# Sediment_Board_single.net
KiCad netlist of a schematic drawn in EAGLE
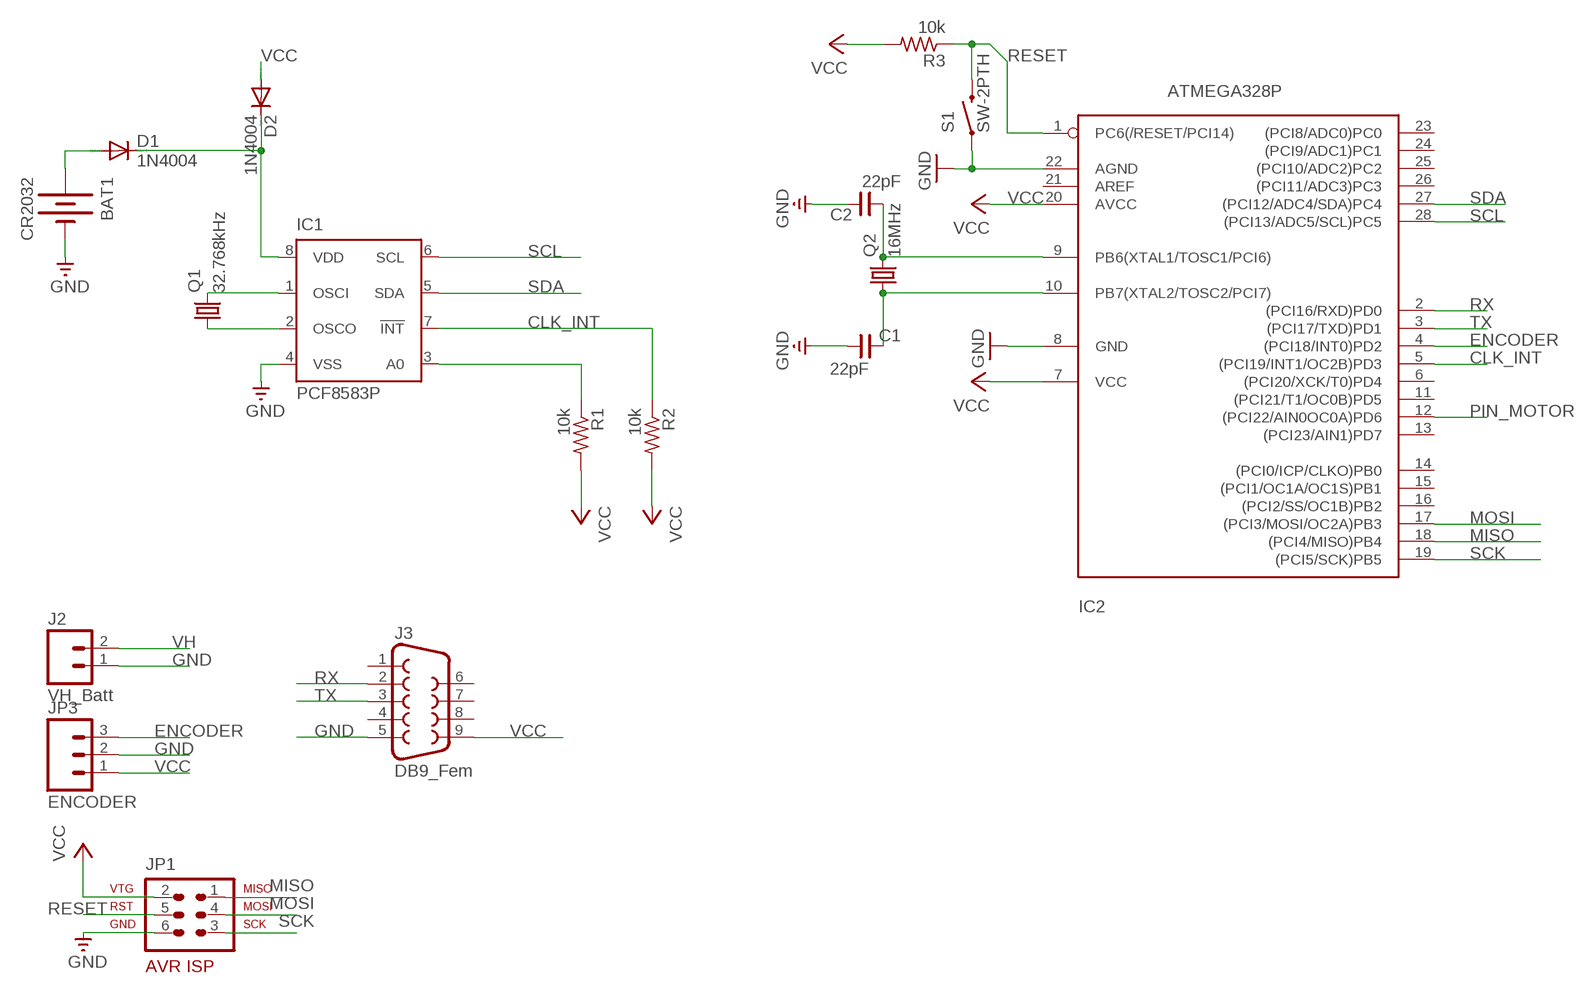
[diagram p0: schematic, sheet 1]
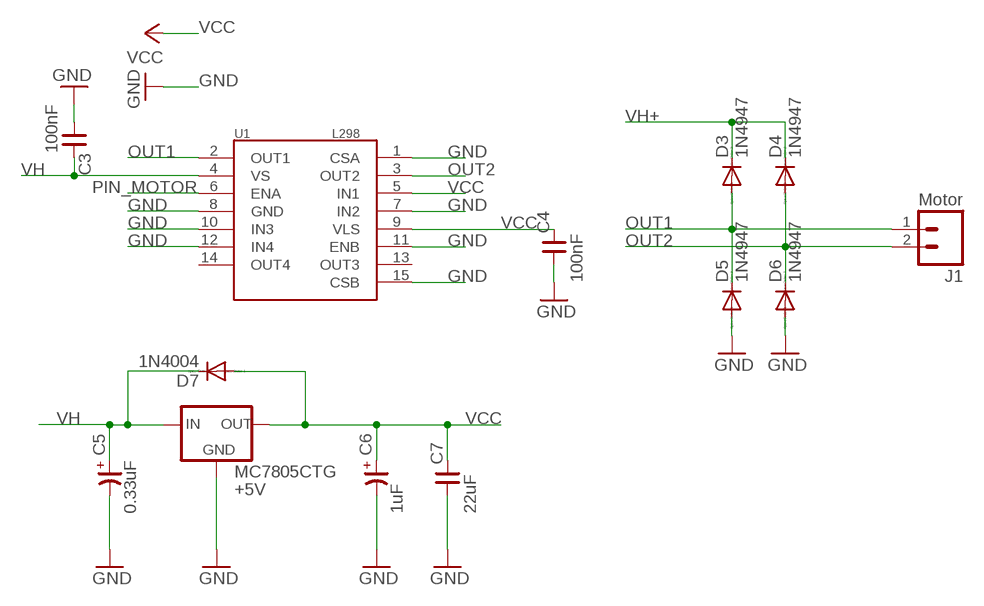
[diagram p1: schematic, sheet 2]

(export (version "E")
  (design (tool "Eeschema 10.0.6"))
  (components
    (comp (ref "C3")
      (value "100nF")
      (footprint "eagle-import:C025-050X025")
      (libsource (lib "eagle-import") (part "CNP-C025-050X025"))
    )
    (comp (ref "C4")
      (value "100nF")
      (footprint "eagle-import:C025-050X025")
      (libsource (lib "eagle-import") (part "CNP-C025-050X025"))
    )
    (comp (ref "C5")
      (value "0.33uF")
      (footprint "eagle-import:TT-025-040")
      (libsource (lib "eagle-import") (part "CP-TT025-040"))
    )
    (comp (ref "C6")
      (value "1uF")
      (footprint "eagle-import:TT-025-040")
      (libsource (lib "eagle-import") (part "CP-TT025-040"))
    )
    (comp (ref "C7")
      (value "22uF")
      (footprint "eagle-import:C025-050X025")
      (libsource (lib "eagle-import") (part "CNP-C025-050X025"))
    )
    (comp (ref "D3")
      (value "1N4947")
      (footprint "eagle-import:DO41-10")
      (libsource (lib "eagle-import") (part "1N4942"))
    )
    (comp (ref "D4")
      (value "1N4947")
      (footprint "eagle-import:DO41-10")
      (libsource (lib "eagle-import") (part "1N4942"))
    )
    (comp (ref "D5")
      (value "1N4947")
      (footprint "eagle-import:DO41-10")
      (libsource (lib "eagle-import") (part "1N4942"))
    )
    (comp (ref "D6")
      (value "1N4947")
      (footprint "eagle-import:DO41-10")
      (libsource (lib "eagle-import") (part "1N4942"))
    )
    (comp (ref "D7")
      (value "1N4004")
      (footprint "eagle-import:DO41-10")
      (libsource (lib "eagle-import") (part "1N4004"))
    )
    (comp (ref "J1")
      (value "Motor")
      (footprint "eagle-import:SCREWTERMINAL-3.5MM-2")
      (libsource (lib "eagle-import") (part "M023.5MM"))
    )
    (comp (ref "MC7805CTG")
      (value "+5V")
      (footprint "eagle-import:78XXL")
      (libsource (lib "eagle-import") (part "V_REG_78XXSIDE"))
    )
    (comp (ref "U1")
      (value "L298")
      (footprint "eagle-import:MULTIWATT15")
      (libsource (lib "eagle-import") (part "L298"))
    )
    (comp (ref "BAT1")
      (value "CR2032")
      (footprint "eagle-import:BATTCOM_20MM_PTH")
      (libsource (lib "eagle-import") (part "BATTERY20PTH"))
    )
    (comp (ref "C1")
      (value "22pF")
      (footprint "eagle-import:C025-050X025")
      (libsource (lib "eagle-import") (part "CNP-C025-050X025"))
    )
    (comp (ref "C2")
      (value "22pF")
      (footprint "eagle-import:C025-050X025")
      (libsource (lib "eagle-import") (part "CNP-C025-050X025"))
    )
    (comp (ref "D1")
      (value "1N4004")
      (footprint "eagle-import:DO41-10")
      (libsource (lib "eagle-import") (part "1N4004"))
    )
    (comp (ref "D2")
      (value "1N4004")
      (footprint "eagle-import:DO41-10")
      (libsource (lib "eagle-import") (part "1N4004"))
    )
    (comp (ref "IC1")
      (value "PCF8583P")
      (footprint "eagle-import:DIL08")
      (libsource (lib "eagle-import") (part "PCF8583P"))
    )
    (comp (ref "IC2")
      (value "ATMEGA328P")
      (footprint "eagle-import:DIL28-3-ROUND")
      (libsource (lib "eagle-import") (part "ATMEGA328PROUND"))
    )
    (comp (ref "J2")
      (value "VH_Batt")
      (footprint "eagle-import:SCREWTERMINAL-3.5MM-2")
      (libsource (lib "eagle-import") (part "M023.5MM"))
    )
    (comp (ref "J3")
      (value "DB9_Fem")
      (footprint "eagle-import:DB9")
      (libsource (lib "eagle-import") (part "DB9FEMALE"))
    )
    (comp (ref "JP1")
      (value "AVR-ISP-6")
      (footprint "eagle-import:AVR-ISP-6")
      (libsource (lib "eagle-import") (part "AVR-ISP-6"))
    )
    (comp (ref "JP3")
      (value "ENCODER")
      (footprint "eagle-import:MOLEX-1X3")
      (libsource (lib "eagle-import") (part "M03POLAR"))
    )
    (comp (ref "Q1")
      (value "32.768kHz")
      (footprint "eagle-import:TC26H")
      (libsource (lib "eagle-import") (part "CRYSTALTC26H"))
    )
    (comp (ref "Q2")
      (value "16MHz")
      (footprint "eagle-import:HC49U70")
      (libsource (lib "eagle-import") (part "CRYSTALHC49U70"))
    )
    (comp (ref "R1")
      (value "10k")
      (footprint "eagle-import:0207_10")
      (libsource (lib "eagle-import") (part "R-US_0207/10"))
    )
    (comp (ref "R2")
      (value "10k")
      (footprint "eagle-import:0207_10")
      (libsource (lib "eagle-import") (part "R-US_0207/10"))
    )
    (comp (ref "R3")
      (value "10k")
      (footprint "eagle-import:0207_10")
      (libsource (lib "eagle-import") (part "R-US_0207/10"))
    )
    (comp (ref "S1")
      (value "SW-2PTH")
      (footprint "eagle-import:TACTILE-PTH")
      (libsource (lib "eagle-import") (part "SWITCH-MOMENTARY-2PTH"))
    )
  )
  (nets
    (net (code "1") (name "CLK_INT") (class "Default")
      (node (ref "IC1") (pin "7") (pinfunction "~{INT}_7") (pintype "open_collector"))
      (node (ref "IC2") (pin "5") (pinfunction "(PCI19/INT1/OC2B)PD3_5") (pintype "bidirectional"))
      (node (ref "R2") (pin "1") (pinfunction "1_1") (pintype "passive"))
    )
    (net (code "2") (name "ENCODER") (class "Default")
      (node (ref "IC2") (pin "4") (pinfunction "(PCI18/INT0)PD2_4") (pintype "bidirectional"))
      (node (ref "JP3") (pin "3") (pinfunction "3_3") (pintype "passive"))
    )
    (net (code "3") (name "GND") (class "Default")
      (node (ref "BAT1") (pin "2") (pinfunction "-_2") (pintype "power_in"))
      (node (ref "C1") (pin "1") (pinfunction "1_1") (pintype "passive"))
      (node (ref "C2") (pin "2") (pinfunction "2_2") (pintype "passive"))
      (node (ref "C3") (pin "1") (pinfunction "1_1") (pintype "passive"))
      (node (ref "C4") (pin "1") (pinfunction "1_1") (pintype "passive"))
      (node (ref "C5") (pin "-") (pinfunction "-_-") (pintype "passive"))
      (node (ref "C6") (pin "-") (pinfunction "-_-") (pintype "passive"))
      (node (ref "C7") (pin "1") (pinfunction "1_1") (pintype "passive"))
      (node (ref "D5") (pin "A") (pinfunction "A_A") (pintype "passive"))
      (node (ref "D6") (pin "A") (pinfunction "A_A") (pintype "passive"))
      (node (ref "IC1") (pin "4") (pinfunction "VSS_4") (pintype "power_in"))
      (node (ref "IC2") (pin "22") (pinfunction "AGND_22") (pintype "bidirectional"))
      (node (ref "IC2") (pin "8") (pinfunction "GND_8") (pintype "bidirectional"))
      (node (ref "J2") (pin "1") (pinfunction "1_1") (pintype "passive"))
      (node (ref "J3") (pin "5") (pinfunction "5_5") (pintype "passive"))
      (node (ref "JP1") (pin "6") (pinfunction "6_6") (pintype "passive"))
      (node (ref "JP3") (pin "2") (pinfunction "2_2") (pintype "passive"))
      (node (ref "MC7805CTG") (pin "GND") (pinfunction "GND_GND") (pintype "input"))
      (node (ref "S1") (pin "1") (pinfunction "1_1") (pintype "passive"))
      (node (ref "U1") (pin "1") (pinfunction "CSA_1") (pintype "bidirectional"))
      (node (ref "U1") (pin "10") (pinfunction "IN3_10") (pintype "bidirectional"))
      (node (ref "U1") (pin "11") (pinfunction "ENB_11") (pintype "bidirectional"))
      (node (ref "U1") (pin "12") (pinfunction "IN4_12") (pintype "bidirectional"))
      (node (ref "U1") (pin "15") (pinfunction "CSB_15") (pintype "bidirectional"))
      (node (ref "U1") (pin "7") (pinfunction "IN2_7") (pintype "bidirectional"))
      (node (ref "U1") (pin "8") (pinfunction "GND_8") (pintype "bidirectional"))
    )
    (net (code "4") (name "MISO") (class "Default")
      (node (ref "IC2") (pin "18") (pinfunction "(PCI4/MISO)PB4_18") (pintype "bidirectional"))
      (node (ref "JP1") (pin "1") (pinfunction "1_1") (pintype "passive"))
    )
    (net (code "5") (name "MOSI") (class "Default")
      (node (ref "IC2") (pin "17") (pinfunction "(PCI3/MOSI/OC2A)PB3_17") (pintype "bidirectional"))
      (node (ref "JP1") (pin "4") (pinfunction "4_4") (pintype "passive"))
    )
    (net (code "6") (name "Net-(BAT1-+)") (class "Default")
      (node (ref "BAT1") (pin "1") (pinfunction "+_1") (pintype "power_in"))
      (node (ref "D1") (pin "A") (pinfunction "A_A") (pintype "passive"))
    )
    (net (code "7") (name "Net-(IC1-A0)") (class "Default")
      (node (ref "IC1") (pin "3") (pinfunction "A0_3") (pintype "input"))
      (node (ref "R1") (pin "1") (pinfunction "1_1") (pintype "passive"))
    )
    (net (code "8") (name "Net-(IC1-OSCI)") (class "Default")
      (node (ref "IC1") (pin "1") (pinfunction "OSCI_1") (pintype "input"))
      (node (ref "Q1") (pin "2") (pinfunction "2_2") (pintype "passive"))
    )
    (net (code "9") (name "Net-(IC1-OSCO)") (class "Default")
      (node (ref "IC1") (pin "2") (pinfunction "OSCO_2") (pintype "output"))
      (node (ref "Q1") (pin "1") (pinfunction "1_1") (pintype "passive"))
    )
    (net (code "10") (name "Net-(IC1-VDD)") (class "Default")
      (node (ref "D1") (pin "C") (pinfunction "C_C") (pintype "passive"))
      (node (ref "D2") (pin "C") (pinfunction "C_C") (pintype "passive"))
      (node (ref "IC1") (pin "8") (pinfunction "VDD_8") (pintype "power_in"))
    )
    (net (code "11") (name "Net-(IC2-PB6(XTAL1{slash}TOSC1{slash}PCI6))") (class "Default")
      (node (ref "C2") (pin "1") (pinfunction "1_1") (pintype "passive"))
      (node (ref "IC2") (pin "9") (pinfunction "PB6(XTAL1/TOSC1/PCI6)_9") (pintype "bidirectional"))
      (node (ref "Q2") (pin "2") (pinfunction "2_2") (pintype "passive"))
    )
    (net (code "12") (name "Net-(IC2-PB7(XTAL2{slash}TOSC2{slash}PCI7))") (class "Default")
      (node (ref "C1") (pin "2") (pinfunction "2_2") (pintype "passive"))
      (node (ref "IC2") (pin "10") (pinfunction "PB7(XTAL2/TOSC2/PCI7)_10") (pintype "bidirectional"))
      (node (ref "Q2") (pin "1") (pinfunction "1_1") (pintype "passive"))
    )
    (net (code "13") (name "OUT1") (class "Default")
      (node (ref "D3") (pin "A") (pinfunction "A_A") (pintype "passive"))
      (node (ref "D5") (pin "C") (pinfunction "C_C") (pintype "passive"))
      (node (ref "J1") (pin "1") (pinfunction "1_1") (pintype "passive"))
      (node (ref "U1") (pin "2") (pinfunction "OUT1_2") (pintype "bidirectional"))
    )
    (net (code "14") (name "OUT2") (class "Default")
      (node (ref "D4") (pin "A") (pinfunction "A_A") (pintype "passive"))
      (node (ref "D6") (pin "C") (pinfunction "C_C") (pintype "passive"))
      (node (ref "J1") (pin "2") (pinfunction "2_2") (pintype "passive"))
      (node (ref "U1") (pin "3") (pinfunction "OUT2_3") (pintype "bidirectional"))
    )
    (net (code "15") (name "PIN_MOTOR") (class "Default")
      (node (ref "IC2") (pin "12") (pinfunction "(PCI22/AIN0OC0A)PD6_12") (pintype "bidirectional"))
      (node (ref "U1") (pin "6") (pinfunction "ENA_6") (pintype "bidirectional"))
    )
    (net (code "16") (name "RESET") (class "Default")
      (node (ref "IC2") (pin "1") (pinfunction "PC6(/RESET/PCI14)_1") (pintype "bidirectional"))
      (node (ref "JP1") (pin "5") (pinfunction "5_5") (pintype "passive"))
      (node (ref "R3") (pin "1") (pinfunction "1_1") (pintype "passive"))
      (node (ref "S1") (pin "3") (pinfunction "2_3") (pintype "passive"))
    )
    (net (code "17") (name "RX") (class "Default")
      (node (ref "IC2") (pin "2") (pinfunction "(PCI16/RXD)PD0_2") (pintype "bidirectional"))
      (node (ref "J3") (pin "2") (pinfunction "2_2") (pintype "passive"))
    )
    (net (code "18") (name "SCK") (class "Default")
      (node (ref "IC2") (pin "19") (pinfunction "(PCI5/SCK)PB5_19") (pintype "bidirectional"))
      (node (ref "JP1") (pin "3") (pinfunction "3_3") (pintype "passive"))
    )
    (net (code "19") (name "SCL") (class "Default")
      (node (ref "IC1") (pin "6") (pinfunction "SCL_6") (pintype "input"))
      (node (ref "IC2") (pin "28") (pinfunction "(PCI13/ADC5/SCL)PC5_28") (pintype "bidirectional"))
    )
    (net (code "20") (name "SDA") (class "Default")
      (node (ref "IC1") (pin "5") (pinfunction "SDA_5") (pintype "bidirectional"))
      (node (ref "IC2") (pin "27") (pinfunction "(PCI12/ADC4/SDA)PC4_27") (pintype "bidirectional"))
    )
    (net (code "21") (name "TX") (class "Default")
      (node (ref "IC2") (pin "3") (pinfunction "(PCI17/TXD)PD1_3") (pintype "bidirectional"))
      (node (ref "J3") (pin "3") (pinfunction "3_3") (pintype "passive"))
    )
    (net (code "22") (name "VCC") (class "Default")
      (node (ref "C4") (pin "2") (pinfunction "2_2") (pintype "passive"))
      (node (ref "C6") (pin "+") (pinfunction "+_+") (pintype "passive"))
      (node (ref "C7") (pin "2") (pinfunction "2_2") (pintype "passive"))
      (node (ref "D2") (pin "A") (pinfunction "A_A") (pintype "passive"))
      (node (ref "D7") (pin "A") (pinfunction "A_A") (pintype "passive"))
      (node (ref "IC2") (pin "20") (pinfunction "AVCC_20") (pintype "bidirectional"))
      (node (ref "IC2") (pin "7") (pinfunction "VCC_7") (pintype "bidirectional"))
      (node (ref "J3") (pin "9") (pinfunction "9_9") (pintype "passive"))
      (node (ref "JP1") (pin "2") (pinfunction "2_2") (pintype "passive"))
      (node (ref "JP3") (pin "1") (pinfunction "1_1") (pintype "passive"))
      (node (ref "MC7805CTG") (pin "OUT") (pinfunction "OUT_OUT") (pintype "output"))
      (node (ref "R1") (pin "2") (pinfunction "2_2") (pintype "passive"))
      (node (ref "R2") (pin "2") (pinfunction "2_2") (pintype "passive"))
      (node (ref "R3") (pin "2") (pinfunction "2_2") (pintype "passive"))
      (node (ref "U1") (pin "5") (pinfunction "IN1_5") (pintype "bidirectional"))
      (node (ref "U1") (pin "9") (pinfunction "VLS_9") (pintype "bidirectional"))
    )
    (net (code "23") (name "VH") (class "Default")
      (node (ref "C3") (pin "2") (pinfunction "2_2") (pintype "passive"))
      (node (ref "C5") (pin "+") (pinfunction "+_+") (pintype "passive"))
      (node (ref "D7") (pin "C") (pinfunction "C_C") (pintype "passive"))
      (node (ref "J2") (pin "2") (pinfunction "2_2") (pintype "passive"))
      (node (ref "MC7805CTG") (pin "IN") (pinfunction "IN_IN") (pintype "input"))
      (node (ref "U1") (pin "4") (pinfunction "VS_4") (pintype "bidirectional"))
    )
    (net (code "24") (name "VH+") (class "Default")
      (node (ref "D3") (pin "C") (pinfunction "C_C") (pintype "passive"))
      (node (ref "D4") (pin "C") (pinfunction "C_C") (pintype "passive"))
    )
    (net (code "25") (name "unconnected-(IC2-(PCI0{slash}ICP{slash}CLKO)PB0-Pad14)") (class "Default")
      (node (ref "IC2") (pin "14") (pinfunction "(PCI0/ICP/CLKO)PB0_14") (pintype "bidirectional"))
    )
    (net (code "26") (name "unconnected-(IC2-(PCI1{slash}OC1A{slash}OC1S)PB1-Pad15)") (class "Default")
      (node (ref "IC2") (pin "15") (pinfunction "(PCI1/OC1A/OC1S)PB1_15") (pintype "bidirectional"))
    )
    (net (code "27") (name "unconnected-(IC2-(PCI2{slash}SS{slash}OC1B)PB2-Pad16)") (class "Default")
      (node (ref "IC2") (pin "16") (pinfunction "(PCI2/SS/OC1B)PB2_16") (pintype "bidirectional"))
    )
    (net (code "28") (name "unconnected-(IC2-(PCI8{slash}ADC0)PC0-Pad23)") (class "Default")
      (node (ref "IC2") (pin "23") (pinfunction "(PCI8/ADC0)PC0_23") (pintype "bidirectional"))
    )
    (net (code "29") (name "unconnected-(IC2-(PCI9{slash}ADC1)PC1-Pad24)") (class "Default")
      (node (ref "IC2") (pin "24") (pinfunction "(PCI9/ADC1)PC1_24") (pintype "bidirectional"))
    )
    (net (code "30") (name "unconnected-(IC2-(PCI10{slash}ADC2)PC2-Pad25)") (class "Default")
      (node (ref "IC2") (pin "25") (pinfunction "(PCI10/ADC2)PC2_25") (pintype "bidirectional"))
    )
    (net (code "31") (name "unconnected-(IC2-(PCI11{slash}ADC3)PC3-Pad26)") (class "Default")
      (node (ref "IC2") (pin "26") (pinfunction "(PCI11/ADC3)PC3_26") (pintype "bidirectional"))
    )
    (net (code "32") (name "unconnected-(IC2-(PCI20{slash}XCK{slash}T0)PD4-Pad6)") (class "Default")
      (node (ref "IC2") (pin "6") (pinfunction "(PCI20/XCK/T0)PD4_6") (pintype "bidirectional"))
    )
    (net (code "33") (name "unconnected-(IC2-(PCI21{slash}T1{slash}OC0B)PD5-Pad11)") (class "Default")
      (node (ref "IC2") (pin "11") (pinfunction "(PCI21/T1/OC0B)PD5_11") (pintype "bidirectional"))
    )
    (net (code "34") (name "unconnected-(IC2-(PCI23{slash}AIN1)PD7-Pad13)") (class "Default")
      (node (ref "IC2") (pin "13") (pinfunction "(PCI23/AIN1)PD7_13") (pintype "bidirectional"))
    )
    (net (code "35") (name "unconnected-(IC2-AREF-Pad21)") (class "Default")
      (node (ref "IC2") (pin "21") (pinfunction "AREF_21") (pintype "bidirectional"))
    )
    (net (code "36") (name "unconnected-(J3-Pad1)") (class "Default")
      (node (ref "J3") (pin "1") (pinfunction "1_1") (pintype "passive"))
    )
    (net (code "37") (name "unconnected-(J3-Pad4)") (class "Default")
      (node (ref "J3") (pin "4") (pinfunction "4_4") (pintype "passive"))
    )
    (net (code "38") (name "unconnected-(J3-Pad6)") (class "Default")
      (node (ref "J3") (pin "6") (pinfunction "6_6") (pintype "passive"))
    )
    (net (code "39") (name "unconnected-(J3-Pad7)") (class "Default")
      (node (ref "J3") (pin "7") (pinfunction "7_7") (pintype "passive"))
    )
    (net (code "40") (name "unconnected-(J3-Pad8)") (class "Default")
      (node (ref "J3") (pin "8") (pinfunction "8_8") (pintype "passive"))
    )
    (net (code "41") (name "unconnected-(U1-OUT3-Pad13)") (class "Default")
      (node (ref "U1") (pin "13") (pinfunction "OUT3_13") (pintype "bidirectional"))
    )
    (net (code "42") (name "unconnected-(U1-OUT4-Pad14)") (class "Default")
      (node (ref "U1") (pin "14") (pinfunction "OUT4_14") (pintype "bidirectional"))
    )
  )
)
